# SCH.net
KiCad netlist of a schematic drawn in Altium Designer
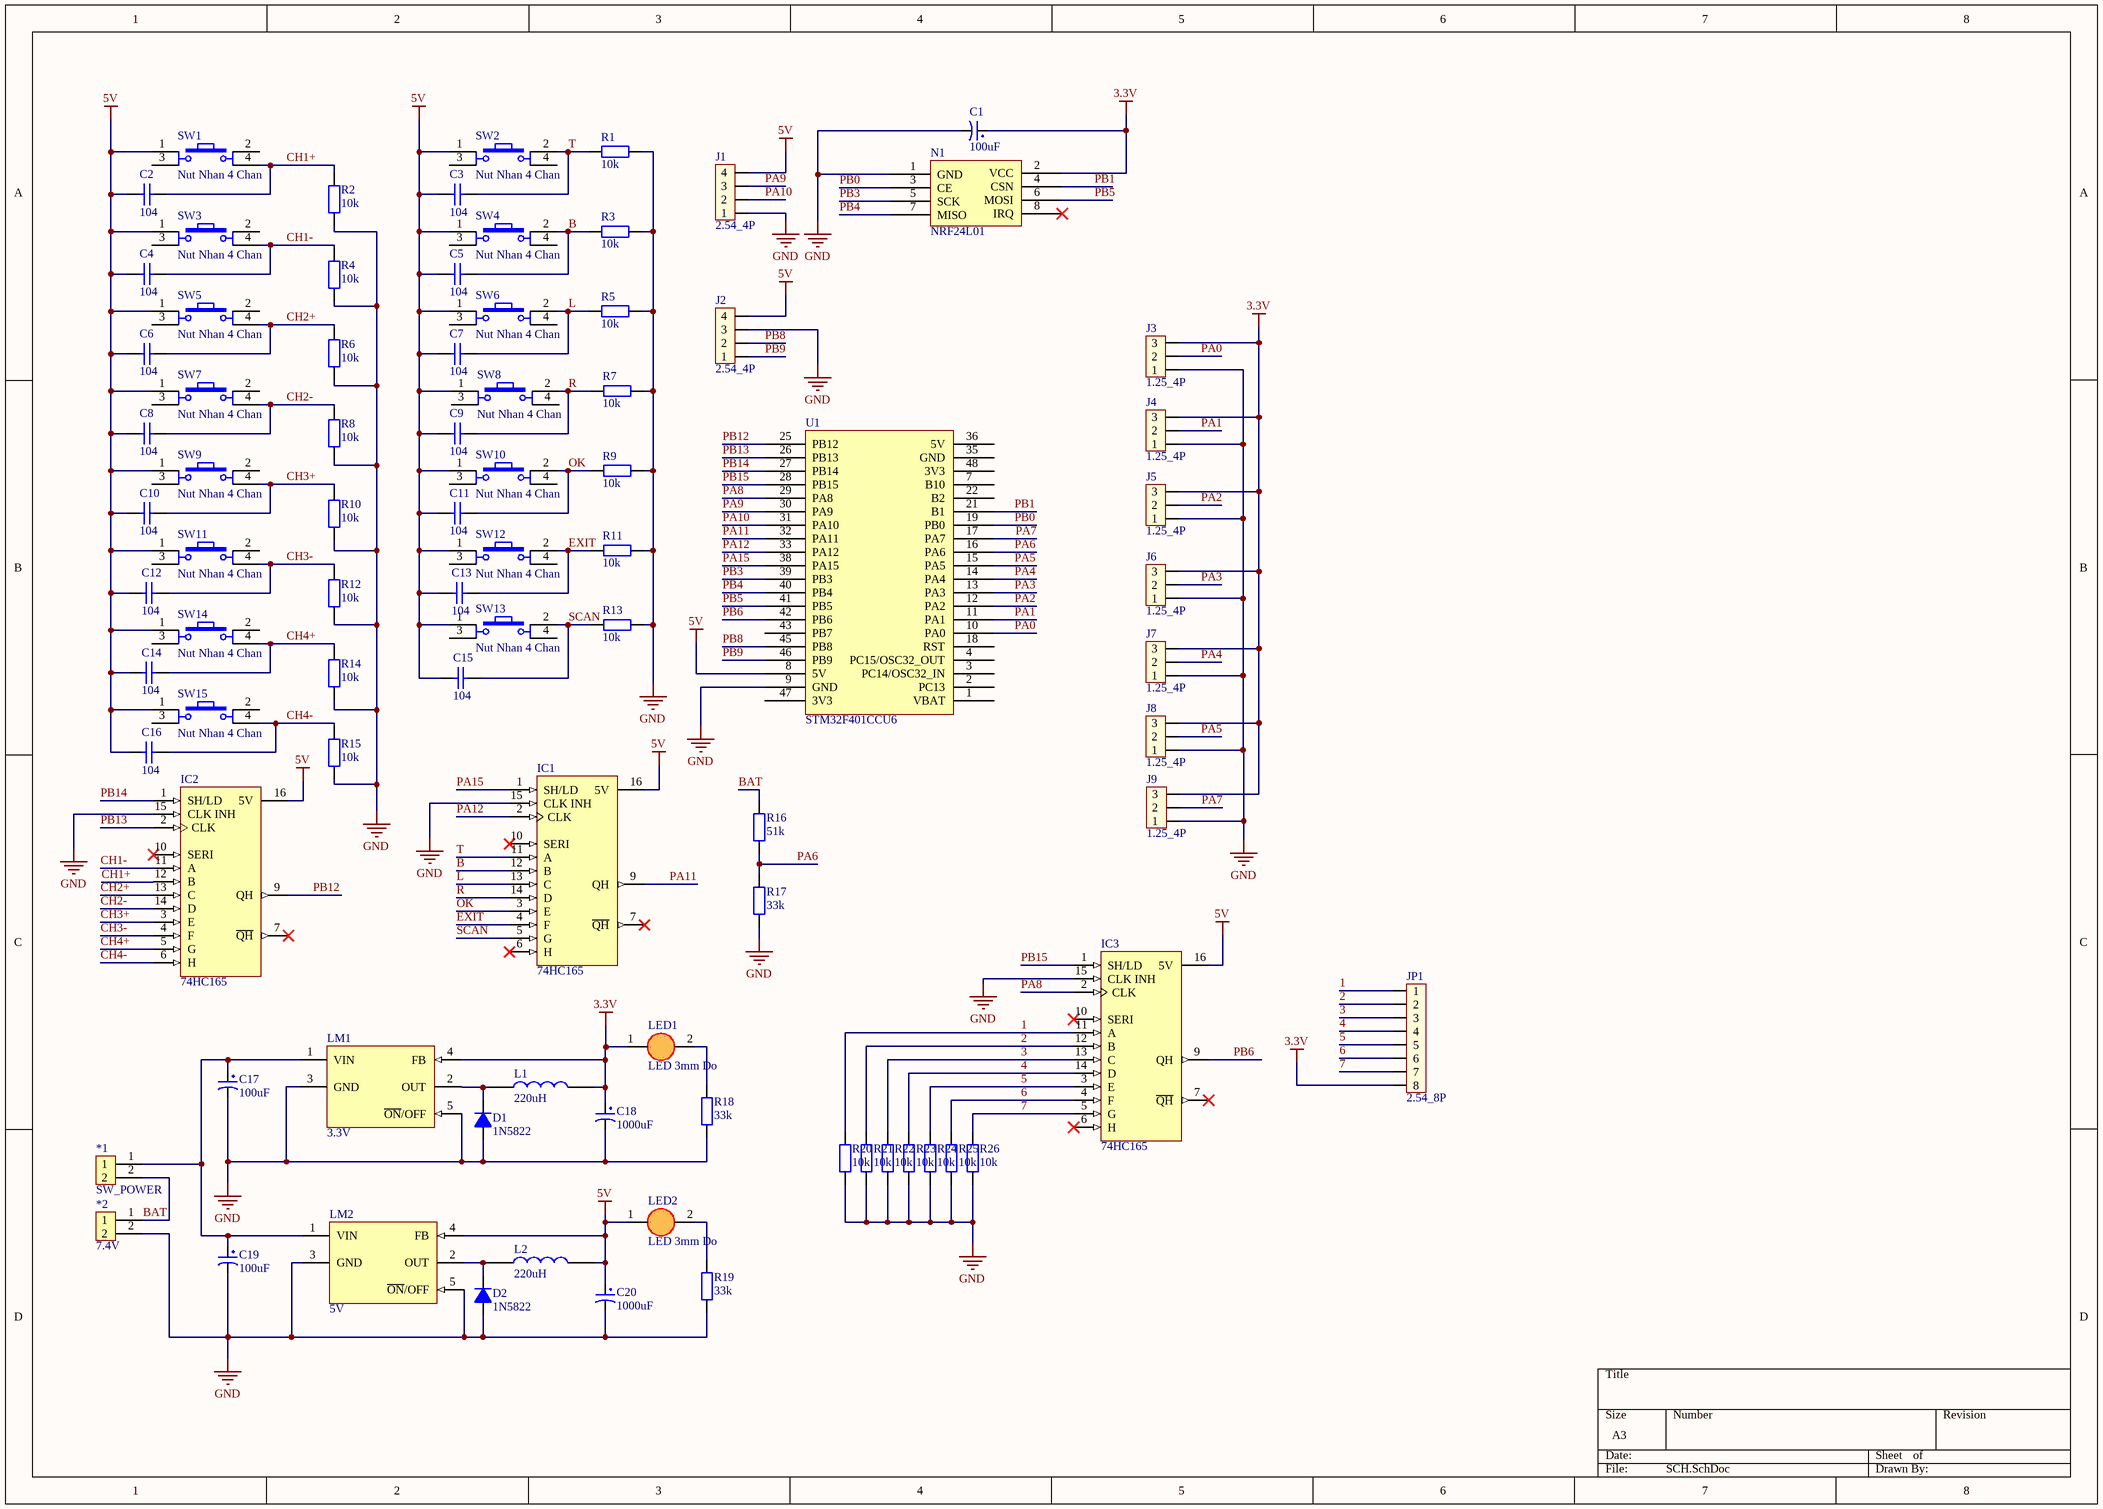
[diagram p0: SCH.SchDoc]

(export (version "E")
  (design (tool "Eeschema 10.0.6"))
  (components
    (comp (ref "*1")
      (value "SW_POWER")
      (footprint "jump don duc_2p")
      (libsource (lib "THU VIEN SCH") (part "jump don duc 2.54_2p"))
    )
    (comp (ref "*2")
      (value "7.4V")
      (footprint "jump don duc_2p")
      (libsource (lib "THU VIEN SCH") (part "jump don duc 2.54_2p"))
    )
    (comp (ref "C1")
      (value "100uF")
      (footprint "tu hoa 5mm")
      (description "Cắm")
      (libsource (lib "THU VIEN SCH") (part "Tu Hoa 100uF 25V 6x11"))
    )
    (comp (ref "C2")
      (value "104")
      (footprint "tu gom")
      (description "Cắm")
      (libsource (lib "THU VIEN SCH") (part "Tu gom 104 50V"))
    )
    (comp (ref "C3")
      (value "104")
      (footprint "tu gom")
      (description "Cắm")
      (libsource (lib "THU VIEN SCH") (part "Tu gom 104 50V"))
    )
    (comp (ref "C4")
      (value "104")
      (footprint "tu gom")
      (description "Cắm")
      (libsource (lib "THU VIEN SCH") (part "Tu gom 104 50V"))
    )
    (comp (ref "C5")
      (value "104")
      (footprint "tu gom")
      (description "Cắm")
      (libsource (lib "THU VIEN SCH") (part "Tu gom 104 50V"))
    )
    (comp (ref "C6")
      (value "104")
      (footprint "tu gom")
      (description "Cắm")
      (libsource (lib "THU VIEN SCH") (part "Tu gom 104 50V"))
    )
    (comp (ref "C7")
      (value "104")
      (footprint "tu gom")
      (description "Cắm")
      (libsource (lib "THU VIEN SCH") (part "Tu gom 104 50V"))
    )
    (comp (ref "C8")
      (value "104")
      (footprint "tu gom")
      (description "Cắm")
      (libsource (lib "THU VIEN SCH") (part "Tu gom 104 50V"))
    )
    (comp (ref "C9")
      (value "104")
      (footprint "tu gom")
      (description "Cắm")
      (libsource (lib "THU VIEN SCH") (part "Tu gom 104 50V"))
    )
    (comp (ref "C10")
      (value "104")
      (footprint "tu gom")
      (description "Cắm")
      (libsource (lib "THU VIEN SCH") (part "Tu gom 104 50V"))
    )
    (comp (ref "C11")
      (value "104")
      (footprint "tu gom")
      (description "Cắm")
      (libsource (lib "THU VIEN SCH") (part "Tu gom 104 50V"))
    )
    (comp (ref "C12")
      (value "104")
      (footprint "tu gom")
      (description "Cắm")
      (libsource (lib "THU VIEN SCH") (part "Tu gom 104 50V"))
    )
    (comp (ref "C13")
      (value "104")
      (footprint "tu gom")
      (description "Cắm")
      (libsource (lib "THU VIEN SCH") (part "Tu gom 104 50V"))
    )
    (comp (ref "C14")
      (value "104")
      (footprint "tu gom")
      (description "Cắm")
      (libsource (lib "THU VIEN SCH") (part "Tu gom 104 50V"))
    )
    (comp (ref "C15")
      (value "104")
      (footprint "tu gom")
      (description "Cắm")
      (libsource (lib "THU VIEN SCH") (part "Tu gom 104 50V"))
    )
    (comp (ref "C16")
      (value "104")
      (footprint "tu gom")
      (description "Cắm")
      (libsource (lib "THU VIEN SCH") (part "Tu gom 104 50V"))
    )
    (comp (ref "C17")
      (value "100uF")
      (footprint "tu hoa 8mm")
      (description "Cắm")
      (libsource (lib "THU VIEN SCH") (part "Tu Hoa 100uF 50V 8x11"))
    )
    (comp (ref "C18")
      (value "1000uF")
      (footprint "tu hoa 8mm")
      (description "Cắm")
      (libsource (lib "THU VIEN SCH") (part "Tu Hoa 1000uF 16V 8x20"))
    )
    (comp (ref "C19")
      (value "100uF")
      (footprint "tu hoa 8mm")
      (description "Cắm")
      (libsource (lib "THU VIEN SCH") (part "Tu Hoa 100uF 50V 8x11"))
    )
    (comp (ref "C20")
      (value "1000uF")
      (footprint "tu hoa 8mm")
      (description "Cắm")
      (libsource (lib "THU VIEN SCH") (part "Tu Hoa 1000uF 16V 8x20"))
    )
    (comp (ref "D1")
      (value "1N5822")
      (footprint "D5A")
      (description "Diode 5A")
      (libsource (lib "syhaunguyen") (part "D5A"))
    )
    (comp (ref "D2")
      (value "1N5822")
      (footprint "D5A")
      (description "Diode 5A")
      (libsource (lib "syhaunguyen") (part "D5A"))
    )
    (comp (ref "IC1")
      (value "74HC165")
      (footprint "DIP16/W0.3")
      (description "8-Bit Parallel In/Serial Out Shift Register")
      (libsource (lib "syhaunguyen") (part "74HC165"))
    )
    (comp (ref "IC2")
      (value "74HC165")
      (footprint "DIP16/W0.3")
      (description "8-Bit Parallel In/Serial Out Shift Register")
      (libsource (lib "syhaunguyen") (part "74HC165"))
    )
    (comp (ref "IC3")
      (value "74HC165")
      (footprint "DIP16/W0.3")
      (description "8-Bit Parallel In/Serial Out Shift Register")
      (libsource (lib "syhaunguyen") (part "74HC165"))
    )
    (comp (ref "J1")
      (value "2.54_4P")
      (footprint "JP4")
      (description "Cắm")
      (libsource (lib "THU VIEN SCH") (part "Jum Don Duc 2.54_4P"))
    )
    (comp (ref "J2")
      (value "2.54_4P")
      (footprint "JP4")
      (description "Cắm")
      (libsource (lib "THU VIEN SCH") (part "Jum Don Duc 2.54_4P"))
    )
    (comp (ref "J3")
      (value "1.25_4P")
      (footprint "ZH1.25 3P")
      (description "Cắm")
      (libsource (lib "THU VIEN SCH") (part "ZH1.25 3P"))
    )
    (comp (ref "J4")
      (value "1.25_4P")
      (footprint "ZH1.25 3P")
      (description "Cắm")
      (libsource (lib "THU VIEN SCH") (part "ZH1.25 3P"))
    )
    (comp (ref "J5")
      (value "1.25_4P")
      (footprint "ZH1.25 3P")
      (description "Cắm")
      (libsource (lib "THU VIEN SCH") (part "ZH1.25 3P"))
    )
    (comp (ref "J6")
      (value "1.25_4P")
      (footprint "ZH1.25 3P")
      (description "Cắm")
      (libsource (lib "THU VIEN SCH") (part "ZH1.25 3P"))
    )
    (comp (ref "J7")
      (value "1.25_4P")
      (footprint "ZH1.25 3P")
      (description "Cắm")
      (libsource (lib "THU VIEN SCH") (part "ZH1.25 3P"))
    )
    (comp (ref "J8")
      (value "1.25_4P")
      (footprint "ZH1.25 3P")
      (description "Cắm")
      (libsource (lib "THU VIEN SCH") (part "ZH1.25 3P"))
    )
    (comp (ref "J9")
      (value "1.25_4P")
      (footprint "ZH1.25 3P")
      (description "Cắm")
      (libsource (lib "THU VIEN SCH") (part "ZH1.25 3P"))
    )
    (comp (ref "JP1")
      (value "2.54_8P")
      (footprint "JP8")
      (description "Cắm")
      (libsource (lib "THU VIEN SCH") (part "Jum Don Duc 2.54_8P"))
    )
    (comp (ref "L1")
      (value "220uH")
      (footprint "CUON CAM 100uH3A")
      (description "Cắm")
      (libsource (lib "THU VIEN SCH") (part "CUON CAM 470uH DIP"))
    )
    (comp (ref "L2")
      (value "220uH")
      (footprint "CUON CAM 100uH3A")
      (description "Cắm")
      (libsource (lib "THU VIEN SCH") (part "CUON CAM 470uH DIP"))
    )
    (comp (ref "LED1")
      (value "LED 3mm Do")
      (footprint "LED 3mm Do")
      (description "Cắm")
      (libsource (lib "THU VIEN SCH") (part "LED 3mm Do"))
    )
    (comp (ref "LED2")
      (value "LED 3mm Do")
      (footprint "LED 3mm Do")
      (description "Cắm")
      (libsource (lib "THU VIEN SCH") (part "LED 3mm Do"))
    )
    (comp (ref "LM1")
      (value "3.3V")
      (footprint "LM2576-5V")
      (description "Cắm")
      (libsource (lib "THU VIEN SCH") (part "LM2576_3.3V."))
    )
    (comp (ref "LM2")
      (value "5V")
      (footprint "LM2576-5V")
      (description "Cắm")
      (libsource (lib "THU VIEN SCH") (part "LM2576_5V"))
    )
    (comp (ref "N1")
      (value "NRF24L01")
      (footprint "NRF24L01")
      (libsource (lib "THU VIEN SCH") (part "NRF24L01"))
    )
    (comp (ref "R1")
      (value "10k")
      (footprint "tro vach 1/4w")
      (description "Căm")
      (libsource (lib "THU VIEN SCH") (part "Tro Vach 1/4W 5% 10k"))
    )
    (comp (ref "R2")
      (value "10k")
      (footprint "tro vach 1/4w")
      (description "Căm")
      (libsource (lib "THU VIEN SCH") (part "Tro Vach 1/4W 5% 10k"))
    )
    (comp (ref "R3")
      (value "10k")
      (footprint "tro vach 1/4w")
      (description "Căm")
      (libsource (lib "THU VIEN SCH") (part "Tro Vach 1/4W 5% 10k"))
    )
    (comp (ref "R4")
      (value "10k")
      (footprint "tro vach 1/4w")
      (description "Căm")
      (libsource (lib "THU VIEN SCH") (part "Tro Vach 1/4W 5% 10k"))
    )
    (comp (ref "R5")
      (value "10k")
      (footprint "tro vach 1/4w")
      (description "Căm")
      (libsource (lib "THU VIEN SCH") (part "Tro Vach 1/4W 5% 10k"))
    )
    (comp (ref "R6")
      (value "10k")
      (footprint "tro vach 1/4w")
      (description "Căm")
      (libsource (lib "THU VIEN SCH") (part "Tro Vach 1/4W 5% 10k"))
    )
    (comp (ref "R7")
      (value "10k")
      (footprint "tro vach 1/4w")
      (description "Căm")
      (libsource (lib "THU VIEN SCH") (part "Tro Vach 1/4W 5% 10k"))
    )
    (comp (ref "R8")
      (value "10k")
      (footprint "tro vach 1/4w")
      (description "Căm")
      (libsource (lib "THU VIEN SCH") (part "Tro Vach 1/4W 5% 10k"))
    )
    (comp (ref "R9")
      (value "10k")
      (footprint "tro vach 1/4w")
      (description "Căm")
      (libsource (lib "THU VIEN SCH") (part "Tro Vach 1/4W 5% 10k"))
    )
    (comp (ref "R10")
      (value "10k")
      (footprint "tro vach 1/4w")
      (description "Căm")
      (libsource (lib "THU VIEN SCH") (part "Tro Vach 1/4W 5% 10k"))
    )
    (comp (ref "R11")
      (value "10k")
      (footprint "tro vach 1/4w")
      (description "Căm")
      (libsource (lib "THU VIEN SCH") (part "Tro Vach 1/4W 5% 10k"))
    )
    (comp (ref "R12")
      (value "10k")
      (footprint "tro vach 1/4w")
      (description "Căm")
      (libsource (lib "THU VIEN SCH") (part "Tro Vach 1/4W 5% 10k"))
    )
    (comp (ref "R13")
      (value "10k")
      (footprint "tro vach 1/4w")
      (description "Căm")
      (libsource (lib "THU VIEN SCH") (part "Tro Vach 1/4W 5% 10k"))
    )
    (comp (ref "R14")
      (value "10k")
      (footprint "tro vach 1/4w")
      (description "Căm")
      (libsource (lib "THU VIEN SCH") (part "Tro Vach 1/4W 5% 10k"))
    )
    (comp (ref "R15")
      (value "10k")
      (footprint "tro vach 1/4w")
      (description "Căm")
      (libsource (lib "THU VIEN SCH") (part "Tro Vach 1/4W 5% 10k"))
    )
    (comp (ref "R16")
      (value "51k")
      (footprint "tro vach 1/4w")
      (description "Căm")
      (libsource (lib "THU VIEN SCH") (part "Tro Vach 1/4W 5% 10k"))
    )
    (comp (ref "R17")
      (value "33k")
      (footprint "tro vach 1/4w")
      (description "Căm")
      (libsource (lib "THU VIEN SCH") (part "Tro Vach 1/4W 5% 10k"))
    )
    (comp (ref "R18")
      (value "33k")
      (footprint "tro vach 1/4w")
      (description "Căm")
      (libsource (lib "THU VIEN SCH") (part "Tro Vach 1/4W 5% 10k"))
    )
    (comp (ref "R19")
      (value "33k")
      (footprint "tro vach 1/4w")
      (description "Căm")
      (libsource (lib "THU VIEN SCH") (part "Tro Vach 1/4W 5% 10k"))
    )
    (comp (ref "R20")
      (value "10k")
      (footprint "tro vach 1/4w")
      (description "Căm")
      (libsource (lib "THU VIEN SCH") (part "Tro Vach 1/4W 5% 10k"))
    )
    (comp (ref "R21")
      (value "10k")
      (footprint "tro vach 1/4w")
      (description "Căm")
      (libsource (lib "THU VIEN SCH") (part "Tro Vach 1/4W 5% 10k"))
    )
    (comp (ref "R22")
      (value "10k")
      (footprint "tro vach 1/4w")
      (description "Căm")
      (libsource (lib "THU VIEN SCH") (part "Tro Vach 1/4W 5% 10k"))
    )
    (comp (ref "R23")
      (value "10k")
      (footprint "tro vach 1/4w")
      (description "Căm")
      (libsource (lib "THU VIEN SCH") (part "Tro Vach 1/4W 5% 10k"))
    )
    (comp (ref "R24")
      (value "10k")
      (footprint "tro vach 1/4w")
      (description "Căm")
      (libsource (lib "THU VIEN SCH") (part "Tro Vach 1/4W 5% 10k"))
    )
    (comp (ref "R25")
      (value "10k")
      (footprint "tro vach 1/4w")
      (description "Căm")
      (libsource (lib "THU VIEN SCH") (part "Tro Vach 1/4W 5% 10k"))
    )
    (comp (ref "R26")
      (value "10k")
      (footprint "tro vach 1/4w")
      (description "Căm")
      (libsource (lib "THU VIEN SCH") (part "Tro Vach 1/4W 5% 10k"))
    )
    (comp (ref "SW1")
      (value "Nut Nhan 4 Chan")
      (footprint "SW4")
      (description "Cắm")
      (libsource (lib "THU VIEN SCH") (part "Nut Nhan 4 Chan"))
    )
    (comp (ref "SW2")
      (value "Nut Nhan 4 Chan")
      (footprint "SW4")
      (description "Cắm")
      (libsource (lib "THU VIEN SCH") (part "Nut Nhan 4 Chan"))
    )
    (comp (ref "SW3")
      (value "Nut Nhan 4 Chan")
      (footprint "SW4")
      (description "Cắm")
      (libsource (lib "THU VIEN SCH") (part "Nut Nhan 4 Chan"))
    )
    (comp (ref "SW4")
      (value "Nut Nhan 4 Chan")
      (footprint "SW4")
      (description "Cắm")
      (libsource (lib "THU VIEN SCH") (part "Nut Nhan 4 Chan"))
    )
    (comp (ref "SW5")
      (value "Nut Nhan 4 Chan")
      (footprint "SW4")
      (description "Cắm")
      (libsource (lib "THU VIEN SCH") (part "Nut Nhan 4 Chan"))
    )
    (comp (ref "SW6")
      (value "Nut Nhan 4 Chan")
      (footprint "SW4")
      (description "Cắm")
      (libsource (lib "THU VIEN SCH") (part "Nut Nhan 4 Chan"))
    )
    (comp (ref "SW7")
      (value "Nut Nhan 4 Chan")
      (footprint "SW4")
      (description "Cắm")
      (libsource (lib "THU VIEN SCH") (part "Nut Nhan 4 Chan"))
    )
    (comp (ref "SW8")
      (value "Nut Nhan 4 Chan")
      (footprint "SW4")
      (description "Cắm")
      (libsource (lib "THU VIEN SCH") (part "Nut Nhan 4 Chan"))
    )
    (comp (ref "SW9")
      (value "Nut Nhan 4 Chan")
      (footprint "SW4")
      (description "Cắm")
      (libsource (lib "THU VIEN SCH") (part "Nut Nhan 4 Chan"))
    )
    (comp (ref "SW10")
      (value "Nut Nhan 4 Chan")
      (footprint "SW4")
      (description "Cắm")
      (libsource (lib "THU VIEN SCH") (part "Nut Nhan 4 Chan"))
    )
    (comp (ref "SW11")
      (value "Nut Nhan 4 Chan")
      (footprint "SW4")
      (description "Cắm")
      (libsource (lib "THU VIEN SCH") (part "Nut Nhan 4 Chan"))
    )
    (comp (ref "SW12")
      (value "Nut Nhan 4 Chan")
      (footprint "SW4")
      (description "Cắm")
      (libsource (lib "THU VIEN SCH") (part "Nut Nhan 4 Chan"))
    )
    (comp (ref "SW13")
      (value "Nut Nhan 4 Chan")
      (footprint "SW4")
      (description "Cắm")
      (libsource (lib "THU VIEN SCH") (part "Nut Nhan 4 Chan"))
    )
    (comp (ref "SW14")
      (value "Nut Nhan 4 Chan")
      (footprint "SW4")
      (description "Cắm")
      (libsource (lib "THU VIEN SCH") (part "Nut Nhan 4 Chan"))
    )
    (comp (ref "SW15")
      (value "Nut Nhan 4 Chan")
      (footprint "SW4")
      (description "Cắm")
      (libsource (lib "THU VIEN SCH") (part "Nut Nhan 4 Chan"))
    )
    (comp (ref "U1")
      (value "STM32F401CCU6")
      (footprint "STM32F401CCU6")
      (libsource (lib "THU VIEN SCH") (part "STM32F401CCU6"))
    )
  )
  (nets
    (net (code "1") (name "/1") (class "Default")
      (node (ref "IC3") (pin "11") (pinfunction "A_11") (pintype "input"))
      (node (ref "JP1") (pin "1") (pinfunction "1_1") (pintype "passive"))
      (node (ref "R20") (pin "2") (pinfunction "2_2") (pintype "passive"))
    )
    (net (code "2") (name "/2") (class "Default")
      (node (ref "IC3") (pin "12") (pinfunction "B_12") (pintype "input"))
      (node (ref "JP1") (pin "2") (pinfunction "2_2") (pintype "passive"))
      (node (ref "R21") (pin "2") (pinfunction "2_2") (pintype "passive"))
    )
    (net (code "3") (name "/3") (class "Default")
      (node (ref "IC3") (pin "13") (pinfunction "C_13") (pintype "input"))
      (node (ref "JP1") (pin "3") (pinfunction "3_3") (pintype "passive"))
      (node (ref "R22") (pin "2") (pinfunction "2_2") (pintype "passive"))
    )
    (net (code "4") (name "/4") (class "Default")
      (node (ref "IC3") (pin "14") (pinfunction "D_14") (pintype "input"))
      (node (ref "JP1") (pin "4") (pinfunction "4_4") (pintype "passive"))
      (node (ref "R23") (pin "2") (pinfunction "2_2") (pintype "passive"))
    )
    (net (code "5") (name "/5") (class "Default")
      (node (ref "IC3") (pin "3") (pinfunction "E_3") (pintype "input"))
      (node (ref "JP1") (pin "5") (pinfunction "5_5") (pintype "passive"))
      (node (ref "R24") (pin "2") (pinfunction "2_2") (pintype "passive"))
    )
    (net (code "6") (name "/6") (class "Default")
      (node (ref "IC3") (pin "4") (pinfunction "F_4") (pintype "input"))
      (node (ref "JP1") (pin "6") (pinfunction "6_6") (pintype "passive"))
      (node (ref "R25") (pin "2") (pinfunction "2_2") (pintype "passive"))
    )
    (net (code "7") (name "/7") (class "Default")
      (node (ref "IC3") (pin "5") (pinfunction "G_5") (pintype "input"))
      (node (ref "JP1") (pin "7") (pinfunction "7_7") (pintype "passive"))
      (node (ref "R26") (pin "2") (pinfunction "2_2") (pintype "passive"))
    )
    (net (code "8") (name "/B") (class "Default")
      (node (ref "C5") (pin "1") (pinfunction "1_1") (pintype "passive"))
      (node (ref "IC1") (pin "12") (pinfunction "B_12") (pintype "input"))
      (node (ref "R3") (pin "1") (pinfunction "1_1") (pintype "passive"))
      (node (ref "SW4") (pin "2") (pintype "passive"))
    )
    (net (code "9") (name "/BAT") (class "Default")
      (node (ref "*1") (pin "2") (pinfunction "2_2") (pintype "passive"))
      (node (ref "*2") (pin "1") (pinfunction "1_1") (pintype "passive"))
      (node (ref "R16") (pin "2") (pinfunction "2_2") (pintype "passive"))
    )
    (net (code "10") (name "/CH1+") (class "Default")
      (node (ref "C2") (pin "1") (pinfunction "1_1") (pintype "passive"))
      (node (ref "IC2") (pin "12") (pinfunction "B_12") (pintype "input"))
      (node (ref "R2") (pin "1") (pinfunction "1_1") (pintype "passive"))
      (node (ref "SW1") (pin "4") (pintype "passive"))
    )
    (net (code "11") (name "/CH1-") (class "Default")
      (node (ref "C4") (pin "1") (pinfunction "1_1") (pintype "passive"))
      (node (ref "IC2") (pin "11") (pinfunction "A_11") (pintype "input"))
      (node (ref "R4") (pin "2") (pinfunction "2_2") (pintype "passive"))
      (node (ref "SW3") (pin "4") (pintype "passive"))
    )
    (net (code "12") (name "/CH2+") (class "Default")
      (node (ref "C6") (pin "1") (pinfunction "1_1") (pintype "passive"))
      (node (ref "IC2") (pin "13") (pinfunction "C_13") (pintype "input"))
      (node (ref "R6") (pin "2") (pinfunction "2_2") (pintype "passive"))
      (node (ref "SW5") (pin "4") (pintype "passive"))
    )
    (net (code "13") (name "/CH2-") (class "Default")
      (node (ref "C8") (pin "1") (pinfunction "1_1") (pintype "passive"))
      (node (ref "IC2") (pin "14") (pinfunction "D_14") (pintype "input"))
      (node (ref "R8") (pin "2") (pinfunction "2_2") (pintype "passive"))
      (node (ref "SW7") (pin "4") (pintype "passive"))
    )
    (net (code "14") (name "/CH3+") (class "Default")
      (node (ref "C10") (pin "1") (pinfunction "1_1") (pintype "passive"))
      (node (ref "IC2") (pin "3") (pinfunction "E_3") (pintype "input"))
      (node (ref "R10") (pin "2") (pinfunction "2_2") (pintype "passive"))
      (node (ref "SW9") (pin "4") (pintype "passive"))
    )
    (net (code "15") (name "/CH3-") (class "Default")
      (node (ref "C12") (pin "1") (pinfunction "1_1") (pintype "passive"))
      (node (ref "IC2") (pin "4") (pinfunction "F_4") (pintype "input"))
      (node (ref "R12") (pin "2") (pinfunction "2_2") (pintype "passive"))
      (node (ref "SW11") (pin "4") (pintype "passive"))
    )
    (net (code "16") (name "/CH4+") (class "Default")
      (node (ref "C14") (pin "1") (pinfunction "1_1") (pintype "passive"))
      (node (ref "IC2") (pin "5") (pinfunction "G_5") (pintype "input"))
      (node (ref "R14") (pin "2") (pinfunction "2_2") (pintype "passive"))
      (node (ref "SW14") (pin "4") (pintype "passive"))
    )
    (net (code "17") (name "/CH4-") (class "Default")
      (node (ref "C16") (pin "1") (pinfunction "1_1") (pintype "passive"))
      (node (ref "IC2") (pin "6") (pinfunction "H_6") (pintype "input"))
      (node (ref "R15") (pin "2") (pinfunction "2_2") (pintype "passive"))
      (node (ref "SW15") (pin "4") (pintype "passive"))
    )
    (net (code "18") (name "/EXIT") (class "Default")
      (node (ref "C13") (pin "1") (pinfunction "1_1") (pintype "passive"))
      (node (ref "IC1") (pin "4") (pinfunction "F_4") (pintype "input"))
      (node (ref "R11") (pin "1") (pinfunction "1_1") (pintype "passive"))
      (node (ref "SW12") (pin "2") (pintype "passive"))
    )
    (net (code "19") (name "/L") (class "Default")
      (node (ref "C7") (pin "1") (pinfunction "1_1") (pintype "passive"))
      (node (ref "IC1") (pin "13") (pinfunction "C_13") (pintype "input"))
      (node (ref "R5") (pin "1") (pinfunction "1_1") (pintype "passive"))
      (node (ref "SW6") (pin "2") (pintype "passive"))
    )
    (net (code "20") (name "/OK") (class "Default")
      (node (ref "C11") (pin "1") (pinfunction "1_1") (pintype "passive"))
      (node (ref "IC1") (pin "3") (pinfunction "E_3") (pintype "input"))
      (node (ref "R9") (pin "1") (pinfunction "1_1") (pintype "passive"))
      (node (ref "SW10") (pin "2") (pintype "passive"))
    )
    (net (code "21") (name "/PA0") (class "Default")
      (node (ref "J3") (pin "2") (pinfunction "2_2") (pintype "passive"))
      (node (ref "U1") (pin "10") (pinfunction "PA0_10") (pintype "passive"))
    )
    (net (code "22") (name "/PA1") (class "Default")
      (node (ref "J4") (pin "2") (pinfunction "2_2") (pintype "passive"))
      (node (ref "U1") (pin "11") (pinfunction "PA1_11") (pintype "passive"))
    )
    (net (code "23") (name "/PA2") (class "Default")
      (node (ref "J5") (pin "2") (pinfunction "2_2") (pintype "passive"))
      (node (ref "U1") (pin "12") (pinfunction "PA2_12") (pintype "passive"))
    )
    (net (code "24") (name "/PA3") (class "Default")
      (node (ref "J6") (pin "2") (pinfunction "2_2") (pintype "passive"))
      (node (ref "U1") (pin "13") (pinfunction "PA3_13") (pintype "passive"))
    )
    (net (code "25") (name "/PA4") (class "Default")
      (node (ref "J7") (pin "2") (pinfunction "2_2") (pintype "passive"))
      (node (ref "U1") (pin "14") (pinfunction "PA4_14") (pintype "passive"))
    )
    (net (code "26") (name "/PA5") (class "Default")
      (node (ref "J8") (pin "2") (pinfunction "2_2") (pintype "passive"))
      (node (ref "U1") (pin "15") (pinfunction "PA5_15") (pintype "passive"))
    )
    (net (code "27") (name "/PA6") (class "Default")
      (node (ref "R16") (pin "1") (pinfunction "1_1") (pintype "passive"))
      (node (ref "R17") (pin "2") (pinfunction "2_2") (pintype "passive"))
      (node (ref "U1") (pin "16") (pinfunction "PA6_16") (pintype "passive"))
    )
    (net (code "28") (name "/PA7") (class "Default")
      (node (ref "J9") (pin "2") (pinfunction "2_2") (pintype "passive"))
      (node (ref "U1") (pin "17") (pinfunction "PA7_17") (pintype "passive"))
    )
    (net (code "29") (name "/PA8") (class "Default")
      (node (ref "IC3") (pin "2") (pinfunction "CLK_2") (pintype "input"))
      (node (ref "U1") (pin "29") (pinfunction "PA8_29") (pintype "passive"))
    )
    (net (code "30") (name "/PA9") (class "Default")
      (node (ref "J1") (pin "3") (pinfunction "3_3") (pintype "passive"))
      (node (ref "U1") (pin "30") (pinfunction "PA9_30") (pintype "passive"))
    )
    (net (code "31") (name "/PA10") (class "Default")
      (node (ref "J1") (pin "2") (pinfunction "2_2") (pintype "passive"))
      (node (ref "U1") (pin "31") (pinfunction "PA10_31") (pintype "passive"))
    )
    (net (code "32") (name "/PA11") (class "Default")
      (node (ref "IC1") (pin "9") (pinfunction "QH_9") (pintype "output"))
      (node (ref "U1") (pin "32") (pinfunction "PA11_32") (pintype "passive"))
    )
    (net (code "33") (name "/PA12") (class "Default")
      (node (ref "IC1") (pin "2") (pinfunction "CLK_2") (pintype "input"))
      (node (ref "U1") (pin "33") (pinfunction "PA12_33") (pintype "passive"))
    )
    (net (code "34") (name "/PA15") (class "Default")
      (node (ref "IC1") (pin "1") (pinfunction "SH/LD_1") (pintype "input"))
      (node (ref "U1") (pin "38") (pinfunction "PA15_38") (pintype "passive"))
    )
    (net (code "35") (name "/PB0") (class "Default")
      (node (ref "N1") (pin "3") (pinfunction "CE_3") (pintype "passive"))
      (node (ref "U1") (pin "19") (pinfunction "PB0_19") (pintype "passive"))
    )
    (net (code "36") (name "/PB1") (class "Default")
      (node (ref "N1") (pin "4") (pinfunction "CSN_4") (pintype "passive"))
      (node (ref "U1") (pin "21") (pinfunction "B1_21") (pintype "passive"))
    )
    (net (code "37") (name "/PB3") (class "Default")
      (node (ref "N1") (pin "5") (pinfunction "SCK_5") (pintype "passive"))
      (node (ref "U1") (pin "39") (pinfunction "PB3_39") (pintype "passive"))
    )
    (net (code "38") (name "/PB4") (class "Default")
      (node (ref "N1") (pin "7") (pinfunction "MISO_7") (pintype "passive"))
      (node (ref "U1") (pin "40") (pinfunction "PB4_40") (pintype "passive"))
    )
    (net (code "39") (name "/PB5") (class "Default")
      (node (ref "N1") (pin "6") (pinfunction "MOSI_6") (pintype "passive"))
      (node (ref "U1") (pin "41") (pinfunction "PB5_41") (pintype "passive"))
    )
    (net (code "40") (name "/PB6") (class "Default")
      (node (ref "IC3") (pin "9") (pinfunction "QH_9") (pintype "output"))
      (node (ref "U1") (pin "42") (pinfunction "PB6_42") (pintype "passive"))
    )
    (net (code "41") (name "/PB8") (class "Default")
      (node (ref "J2") (pin "2") (pinfunction "2_2") (pintype "passive"))
      (node (ref "U1") (pin "45") (pinfunction "PB8_45") (pintype "passive"))
    )
    (net (code "42") (name "/PB9") (class "Default")
      (node (ref "J2") (pin "1") (pinfunction "1_1") (pintype "passive"))
      (node (ref "U1") (pin "46") (pinfunction "PB9_46") (pintype "passive"))
    )
    (net (code "43") (name "/PB12") (class "Default")
      (node (ref "IC2") (pin "9") (pinfunction "QH_9") (pintype "output"))
      (node (ref "U1") (pin "25") (pinfunction "PB12_25") (pintype "passive"))
    )
    (net (code "44") (name "/PB13") (class "Default")
      (node (ref "IC2") (pin "2") (pinfunction "CLK_2") (pintype "input"))
      (node (ref "U1") (pin "26") (pinfunction "PB13_26") (pintype "passive"))
    )
    (net (code "45") (name "/PB14") (class "Default")
      (node (ref "IC2") (pin "1") (pinfunction "SH/LD_1") (pintype "input"))
      (node (ref "U1") (pin "27") (pinfunction "PB14_27") (pintype "passive"))
    )
    (net (code "46") (name "/PB15") (class "Default")
      (node (ref "IC3") (pin "1") (pinfunction "SH/LD_1") (pintype "input"))
      (node (ref "U1") (pin "28") (pinfunction "PB15_28") (pintype "passive"))
    )
    (net (code "47") (name "/R") (class "Default")
      (node (ref "C9") (pin "1") (pinfunction "1_1") (pintype "passive"))
      (node (ref "IC1") (pin "14") (pinfunction "D_14") (pintype "input"))
      (node (ref "R7") (pin "1") (pinfunction "1_1") (pintype "passive"))
      (node (ref "SW8") (pin "2") (pintype "passive"))
    )
    (net (code "48") (name "/SCAN") (class "Default")
      (node (ref "C15") (pin "1") (pinfunction "1_1") (pintype "passive"))
      (node (ref "IC1") (pin "5") (pinfunction "G_5") (pintype "input"))
      (node (ref "R13") (pin "1") (pinfunction "1_1") (pintype "passive"))
      (node (ref "SW13") (pin "2") (pintype "passive"))
    )
    (net (code "49") (name "/T") (class "Default")
      (node (ref "C3") (pin "1") (pinfunction "1_1") (pintype "passive"))
      (node (ref "IC1") (pin "11") (pinfunction "A_11") (pintype "input"))
      (node (ref "R1") (pin "1") (pinfunction "1_1") (pintype "passive"))
      (node (ref "SW2") (pin "2") (pintype "passive"))
    )
    (net (code "50") (name "3.3V") (class "Default")
      (node (ref "C1") (pin "1") (pinfunction "1_1") (pintype "passive"))
      (node (ref "C18") (pin "1") (pinfunction "1_1") (pintype "passive"))
      (node (ref "J3") (pin "3") (pinfunction "3_3") (pintype "passive"))
      (node (ref "J4") (pin "3") (pinfunction "3_3") (pintype "passive"))
      (node (ref "J5") (pin "3") (pinfunction "3_3") (pintype "passive"))
      (node (ref "J6") (pin "3") (pinfunction "3_3") (pintype "passive"))
      (node (ref "J7") (pin "3") (pinfunction "3_3") (pintype "passive"))
      (node (ref "J8") (pin "3") (pinfunction "3_3") (pintype "passive"))
      (node (ref "J9") (pin "3") (pinfunction "3_3") (pintype "passive"))
      (node (ref "JP1") (pin "8") (pinfunction "8_8") (pintype "passive"))
      (node (ref "L1") (pin "2") (pinfunction "2_2") (pintype "passive"))
      (node (ref "LED1") (pin "1") (pinfunction "A_1") (pintype "passive"))
      (node (ref "LM1") (pin "4") (pinfunction "FB_4") (pintype "input"))
      (node (ref "N1") (pin "2") (pinfunction "VCC_2") (pintype "passive"))
    )
    (net (code "51") (name "5V") (class "Default")
      (node (ref "C10") (pin "2") (pinfunction "2_2") (pintype "passive"))
      (node (ref "C11") (pin "2") (pinfunction "2_2") (pintype "passive"))
      (node (ref "C12") (pin "2") (pinfunction "2_2") (pintype "passive"))
      (node (ref "C13") (pin "2") (pinfunction "2_2") (pintype "passive"))
      (node (ref "C14") (pin "2") (pinfunction "2_2") (pintype "passive"))
      (node (ref "C15") (pin "2") (pinfunction "2_2") (pintype "passive"))
      (node (ref "C16") (pin "2") (pinfunction "2_2") (pintype "passive"))
      (node (ref "C2") (pin "2") (pinfunction "2_2") (pintype "passive"))
      (node (ref "C20") (pin "1") (pinfunction "1_1") (pintype "passive"))
      (node (ref "C3") (pin "2") (pinfunction "2_2") (pintype "passive"))
      (node (ref "C4") (pin "2") (pinfunction "2_2") (pintype "passive"))
      (node (ref "C5") (pin "2") (pinfunction "2_2") (pintype "passive"))
      (node (ref "C6") (pin "2") (pinfunction "2_2") (pintype "passive"))
      (node (ref "C7") (pin "2") (pinfunction "2_2") (pintype "passive"))
      (node (ref "C8") (pin "2") (pinfunction "2_2") (pintype "passive"))
      (node (ref "C9") (pin "2") (pinfunction "2_2") (pintype "passive"))
      (node (ref "IC1") (pin "16") (pinfunction "5V_16") (pintype "power_in"))
      (node (ref "IC2") (pin "16") (pinfunction "5V_16") (pintype "power_in"))
      (node (ref "IC3") (pin "16") (pinfunction "5V_16") (pintype "power_in"))
      (node (ref "J1") (pin "4") (pinfunction "4_4") (pintype "passive"))
      (node (ref "J2") (pin "4") (pinfunction "4_4") (pintype "passive"))
      (node (ref "L2") (pin "2") (pinfunction "2_2") (pintype "passive"))
      (node (ref "LED2") (pin "1") (pinfunction "A_1") (pintype "passive"))
      (node (ref "LM2") (pin "4") (pinfunction "FB_4") (pintype "input"))
      (node (ref "SW1") (pin "1") (pintype "passive"))
      (node (ref "SW10") (pin "1") (pintype "passive"))
      (node (ref "SW11") (pin "1") (pintype "passive"))
      (node (ref "SW12") (pin "1") (pintype "passive"))
      (node (ref "SW13") (pin "1") (pintype "passive"))
      (node (ref "SW14") (pin "1") (pintype "passive"))
      (node (ref "SW15") (pin "1") (pintype "passive"))
      (node (ref "SW2") (pin "1") (pintype "passive"))
      (node (ref "SW3") (pin "1") (pintype "passive"))
      (node (ref "SW4") (pin "1") (pintype "passive"))
      (node (ref "SW5") (pin "1") (pintype "passive"))
      (node (ref "SW6") (pin "1") (pintype "passive"))
      (node (ref "SW7") (pin "1") (pintype "passive"))
      (node (ref "SW8") (pin "1") (pintype "passive"))
      (node (ref "SW9") (pin "1") (pintype "passive"))
      (node (ref "U1") (pin "8") (pinfunction "5V_8") (pintype "passive"))
    )
    (net (code "52") (name "GND") (class "Default")
      (node (ref "*2") (pin "2") (pinfunction "2_2") (pintype "passive"))
      (node (ref "C1") (pin "2") (pinfunction "2_2") (pintype "passive"))
      (node (ref "C17") (pin "2") (pinfunction "2_2") (pintype "passive"))
      (node (ref "C18") (pin "2") (pinfunction "2_2") (pintype "passive"))
      (node (ref "C19") (pin "2") (pinfunction "2_2") (pintype "passive"))
      (node (ref "C20") (pin "2") (pinfunction "2_2") (pintype "passive"))
      (node (ref "D1") (pin "1") (pinfunction "A_1") (pintype "passive"))
      (node (ref "D2") (pin "1") (pinfunction "A_1") (pintype "passive"))
      (node (ref "IC1") (pin "15") (pinfunction "CLK_INH_15") (pintype "input"))
      (node (ref "IC1") (pin "8") (pinfunction "GND_8") (pintype "power_in"))
      (node (ref "IC2") (pin "15") (pinfunction "CLK_INH_15") (pintype "input"))
      (node (ref "IC2") (pin "8") (pinfunction "GND_8") (pintype "power_in"))
      (node (ref "IC3") (pin "15") (pinfunction "CLK_INH_15") (pintype "input"))
      (node (ref "IC3") (pin "8") (pinfunction "GND_8") (pintype "power_in"))
      (node (ref "J1") (pin "1") (pinfunction "1_1") (pintype "passive"))
      (node (ref "J2") (pin "3") (pinfunction "3_3") (pintype "passive"))
      (node (ref "J3") (pin "1") (pinfunction "1_1") (pintype "passive"))
      (node (ref "J4") (pin "1") (pinfunction "1_1") (pintype "passive"))
      (node (ref "J5") (pin "1") (pinfunction "1_1") (pintype "passive"))
      (node (ref "J6") (pin "1") (pinfunction "1_1") (pintype "passive"))
      (node (ref "J7") (pin "1") (pinfunction "1_1") (pintype "passive"))
      (node (ref "J8") (pin "1") (pinfunction "1_1") (pintype "passive"))
      (node (ref "J9") (pin "1") (pinfunction "1_1") (pintype "passive"))
      (node (ref "LM1") (pin "3") (pinfunction "GND_3") (pintype "power_in"))
      (node (ref "LM1") (pin "5") (pinfunction "~{ON}/OFF_5") (pintype "input"))
      (node (ref "LM2") (pin "3") (pinfunction "GND_3") (pintype "power_in"))
      (node (ref "LM2") (pin "5") (pinfunction "~{ON}/OFF_5") (pintype "input"))
      (node (ref "N1") (pin "1") (pinfunction "GND_1") (pintype "passive"))
      (node (ref "R1") (pin "2") (pinfunction "2_2") (pintype "passive"))
      (node (ref "R10") (pin "1") (pinfunction "1_1") (pintype "passive"))
      (node (ref "R11") (pin "2") (pinfunction "2_2") (pintype "passive"))
      (node (ref "R12") (pin "1") (pinfunction "1_1") (pintype "passive"))
      (node (ref "R13") (pin "2") (pinfunction "2_2") (pintype "passive"))
      (node (ref "R14") (pin "1") (pinfunction "1_1") (pintype "passive"))
      (node (ref "R15") (pin "1") (pinfunction "1_1") (pintype "passive"))
      (node (ref "R17") (pin "1") (pinfunction "1_1") (pintype "passive"))
      (node (ref "R18") (pin "2") (pinfunction "2_2") (pintype "passive"))
      (node (ref "R19") (pin "2") (pinfunction "2_2") (pintype "passive"))
      (node (ref "R2") (pin "2") (pinfunction "2_2") (pintype "passive"))
      (node (ref "R20") (pin "1") (pinfunction "1_1") (pintype "passive"))
      (node (ref "R21") (pin "1") (pinfunction "1_1") (pintype "passive"))
      (node (ref "R22") (pin "1") (pinfunction "1_1") (pintype "passive"))
      (node (ref "R23") (pin "1") (pinfunction "1_1") (pintype "passive"))
      (node (ref "R24") (pin "1") (pinfunction "1_1") (pintype "passive"))
      (node (ref "R25") (pin "1") (pinfunction "1_1") (pintype "passive"))
      (node (ref "R26") (pin "1") (pinfunction "1_1") (pintype "passive"))
      (node (ref "R3") (pin "2") (pinfunction "2_2") (pintype "passive"))
      (node (ref "R4") (pin "1") (pinfunction "1_1") (pintype "passive"))
      (node (ref "R5") (pin "2") (pinfunction "2_2") (pintype "passive"))
      (node (ref "R6") (pin "1") (pinfunction "1_1") (pintype "passive"))
      (node (ref "R7") (pin "2") (pinfunction "2_2") (pintype "passive"))
      (node (ref "R8") (pin "1") (pinfunction "1_1") (pintype "passive"))
      (node (ref "R9") (pin "2") (pinfunction "2_2") (pintype "passive"))
      (node (ref "U1") (pin "9") (pinfunction "GND_9") (pintype "passive"))
    )
    (net (code "53") (name "Net-(D1-K)") (class "Default")
      (node (ref "D1") (pin "2") (pinfunction "K_2") (pintype "passive"))
      (node (ref "L1") (pin "1") (pinfunction "1_1") (pintype "passive"))
      (node (ref "LM1") (pin "2") (pinfunction "OUT_2") (pintype "power_in"))
    )
    (net (code "54") (name "Net-(D2-K)") (class "Default")
      (node (ref "D2") (pin "2") (pinfunction "K_2") (pintype "passive"))
      (node (ref "L2") (pin "1") (pinfunction "1_1") (pintype "passive"))
      (node (ref "LM2") (pin "2") (pinfunction "OUT_2") (pintype "power_in"))
    )
    (net (code "55") (name "Net-(LED1-K)") (class "Default")
      (node (ref "LED1") (pin "2") (pinfunction "K_2") (pintype "passive"))
      (node (ref "R18") (pin "1") (pinfunction "1_1") (pintype "passive"))
    )
    (net (code "56") (name "Net-(LED2-K)") (class "Default")
      (node (ref "LED2") (pin "2") (pinfunction "K_2") (pintype "passive"))
      (node (ref "R19") (pin "1") (pinfunction "1_1") (pintype "passive"))
    )
    (net (code "57") (name "Net-(LM1-VIN)") (class "Default")
      (node (ref "*1") (pin "1") (pinfunction "1_1") (pintype "passive"))
      (node (ref "C17") (pin "1") (pinfunction "1_1") (pintype "passive"))
      (node (ref "C19") (pin "1") (pinfunction "1_1") (pintype "passive"))
      (node (ref "LM1") (pin "1") (pinfunction "VIN_1") (pintype "power_in"))
      (node (ref "LM2") (pin "1") (pinfunction "VIN_1") (pintype "power_in"))
    )
    (net (code "58") (name "unconnected-(IC1-H-Pad6)") (class "Default")
      (node (ref "IC1") (pin "6") (pinfunction "H_6") (pintype "input+no_connect"))
    )
    (net (code "59") (name "unconnected-(IC1-SERI-Pad10)") (class "Default")
      (node (ref "IC1") (pin "10") (pinfunction "SERI_10") (pintype "input+no_connect"))
    )
    (net (code "60") (name "unconnected-(IC1-~{QH}-Pad7)") (class "Default")
      (node (ref "IC1") (pin "7") (pinfunction "~{QH}_7") (pintype "output+no_connect"))
    )
    (net (code "61") (name "unconnected-(IC2-SERI-Pad10)") (class "Default")
      (node (ref "IC2") (pin "10") (pinfunction "SERI_10") (pintype "input+no_connect"))
    )
    (net (code "62") (name "unconnected-(IC2-~{QH}-Pad7)") (class "Default")
      (node (ref "IC2") (pin "7") (pinfunction "~{QH}_7") (pintype "output+no_connect"))
    )
    (net (code "63") (name "unconnected-(IC3-H-Pad6)") (class "Default")
      (node (ref "IC3") (pin "6") (pinfunction "H_6") (pintype "input+no_connect"))
    )
    (net (code "64") (name "unconnected-(IC3-SERI-Pad10)") (class "Default")
      (node (ref "IC3") (pin "10") (pinfunction "SERI_10") (pintype "input+no_connect"))
    )
    (net (code "65") (name "unconnected-(IC3-~{QH}-Pad7)") (class "Default")
      (node (ref "IC3") (pin "7") (pinfunction "~{QH}_7") (pintype "output+no_connect"))
    )
    (net (code "66") (name "unconnected-(N1-IRQ-Pad8)") (class "Default")
      (node (ref "N1") (pin "8") (pinfunction "IRQ_8") (pintype "passive+no_connect"))
    )
    (net (code "67") (name "unconnected-(SW1-Pad2)") (class "Default")
      (node (ref "SW1") (pin "2") (pintype "passive"))
    )
    (net (code "68") (name "unconnected-(SW1-Pad3)") (class "Default")
      (node (ref "SW1") (pin "3") (pintype "passive"))
    )
    (net (code "69") (name "unconnected-(SW2-Pad3)") (class "Default")
      (node (ref "SW2") (pin "3") (pintype "passive"))
    )
    (net (code "70") (name "unconnected-(SW2-Pad4)") (class "Default")
      (node (ref "SW2") (pin "4") (pintype "passive"))
    )
    (net (code "71") (name "unconnected-(SW3-Pad2)") (class "Default")
      (node (ref "SW3") (pin "2") (pintype "passive"))
    )
    (net (code "72") (name "unconnected-(SW3-Pad3)") (class "Default")
      (node (ref "SW3") (pin "3") (pintype "passive"))
    )
    (net (code "73") (name "unconnected-(SW4-Pad3)") (class "Default")
      (node (ref "SW4") (pin "3") (pintype "passive"))
    )
    (net (code "74") (name "unconnected-(SW4-Pad4)") (class "Default")
      (node (ref "SW4") (pin "4") (pintype "passive"))
    )
    (net (code "75") (name "unconnected-(SW5-Pad2)") (class "Default")
      (node (ref "SW5") (pin "2") (pintype "passive"))
    )
    (net (code "76") (name "unconnected-(SW5-Pad3)") (class "Default")
      (node (ref "SW5") (pin "3") (pintype "passive"))
    )
    (net (code "77") (name "unconnected-(SW6-Pad3)") (class "Default")
      (node (ref "SW6") (pin "3") (pintype "passive"))
    )
    (net (code "78") (name "unconnected-(SW6-Pad4)") (class "Default")
      (node (ref "SW6") (pin "4") (pintype "passive"))
    )
    (net (code "79") (name "unconnected-(SW7-Pad2)") (class "Default")
      (node (ref "SW7") (pin "2") (pintype "passive"))
    )
    (net (code "80") (name "unconnected-(SW7-Pad3)") (class "Default")
      (node (ref "SW7") (pin "3") (pintype "passive"))
    )
    (net (code "81") (name "unconnected-(SW8-Pad3)") (class "Default")
      (node (ref "SW8") (pin "3") (pintype "passive"))
    )
    (net (code "82") (name "unconnected-(SW8-Pad4)") (class "Default")
      (node (ref "SW8") (pin "4") (pintype "passive"))
    )
    (net (code "83") (name "unconnected-(SW9-Pad2)") (class "Default")
      (node (ref "SW9") (pin "2") (pintype "passive"))
    )
    (net (code "84") (name "unconnected-(SW9-Pad3)") (class "Default")
      (node (ref "SW9") (pin "3") (pintype "passive"))
    )
    (net (code "85") (name "unconnected-(SW10-Pad3)") (class "Default")
      (node (ref "SW10") (pin "3") (pintype "passive"))
    )
    (net (code "86") (name "unconnected-(SW10-Pad4)") (class "Default")
      (node (ref "SW10") (pin "4") (pintype "passive"))
    )
    (net (code "87") (name "unconnected-(SW11-Pad2)") (class "Default")
      (node (ref "SW11") (pin "2") (pintype "passive"))
    )
    (net (code "88") (name "unconnected-(SW11-Pad3)") (class "Default")
      (node (ref "SW11") (pin "3") (pintype "passive"))
    )
    (net (code "89") (name "unconnected-(SW12-Pad3)") (class "Default")
      (node (ref "SW12") (pin "3") (pintype "passive"))
    )
    (net (code "90") (name "unconnected-(SW12-Pad4)") (class "Default")
      (node (ref "SW12") (pin "4") (pintype "passive"))
    )
    (net (code "91") (name "unconnected-(SW13-Pad3)") (class "Default")
      (node (ref "SW13") (pin "3") (pintype "passive"))
    )
    (net (code "92") (name "unconnected-(SW13-Pad4)") (class "Default")
      (node (ref "SW13") (pin "4") (pintype "passive"))
    )
    (net (code "93") (name "unconnected-(SW14-Pad2)") (class "Default")
      (node (ref "SW14") (pin "2") (pintype "passive"))
    )
    (net (code "94") (name "unconnected-(SW14-Pad3)") (class "Default")
      (node (ref "SW14") (pin "3") (pintype "passive"))
    )
    (net (code "95") (name "unconnected-(SW15-Pad2)") (class "Default")
      (node (ref "SW15") (pin "2") (pintype "passive"))
    )
    (net (code "96") (name "unconnected-(SW15-Pad3)") (class "Default")
      (node (ref "SW15") (pin "3") (pintype "passive"))
    )
    (net (code "97") (name "unconnected-(U1-3V3-Pad47)") (class "Default")
      (node (ref "U1") (pin "47") (pinfunction "3V3_47") (pintype "passive"))
    )
    (net (code "98") (name "unconnected-(U1-3V3-Pad48)") (class "Default")
      (node (ref "U1") (pin "48") (pinfunction "3V3_48") (pintype "passive"))
    )
    (net (code "99") (name "unconnected-(U1-5V-Pad36)") (class "Default")
      (node (ref "U1") (pin "36") (pinfunction "5V_36") (pintype "passive"))
    )
    (net (code "100") (name "unconnected-(U1-B2-Pad22)") (class "Default")
      (node (ref "U1") (pin "22") (pinfunction "B2_22") (pintype "passive"))
    )
    (net (code "101") (name "unconnected-(U1-B10-Pad7)") (class "Default")
      (node (ref "U1") (pin "7") (pinfunction "B10_7") (pintype "passive"))
    )
    (net (code "102") (name "unconnected-(U1-GND-Pad35)") (class "Default")
      (node (ref "U1") (pin "35") (pinfunction "GND_35") (pintype "passive"))
    )
    (net (code "103") (name "unconnected-(U1-PB7-Pad43)") (class "Default")
      (node (ref "U1") (pin "43") (pinfunction "PB7_43") (pintype "passive"))
    )
    (net (code "104") (name "unconnected-(U1-PC13-Pad2)") (class "Default")
      (node (ref "U1") (pin "2") (pinfunction "PC13_2") (pintype "passive"))
    )
    (net (code "105") (name "unconnected-(U1-PC14{slash}OSC32_IN-Pad3)") (class "Default")
      (node (ref "U1") (pin "3") (pinfunction "PC14/OSC32_IN_3") (pintype "passive"))
    )
    (net (code "106") (name "unconnected-(U1-PC15{slash}OSC32_OUT-Pad4)") (class "Default")
      (node (ref "U1") (pin "4") (pinfunction "PC15/OSC32_OUT_4") (pintype "passive"))
    )
    (net (code "107") (name "unconnected-(U1-RST-Pad18)") (class "Default")
      (node (ref "U1") (pin "18") (pinfunction "RST_18") (pintype "passive"))
    )
    (net (code "108") (name "unconnected-(U1-VBAT-Pad1)") (class "Default")
      (node (ref "U1") (pin "1") (pinfunction "VBAT_1") (pintype "passive"))
    )
  )
)
